# HV_Side.net
KiCad netlist of a schematic drawn in Altium Designer
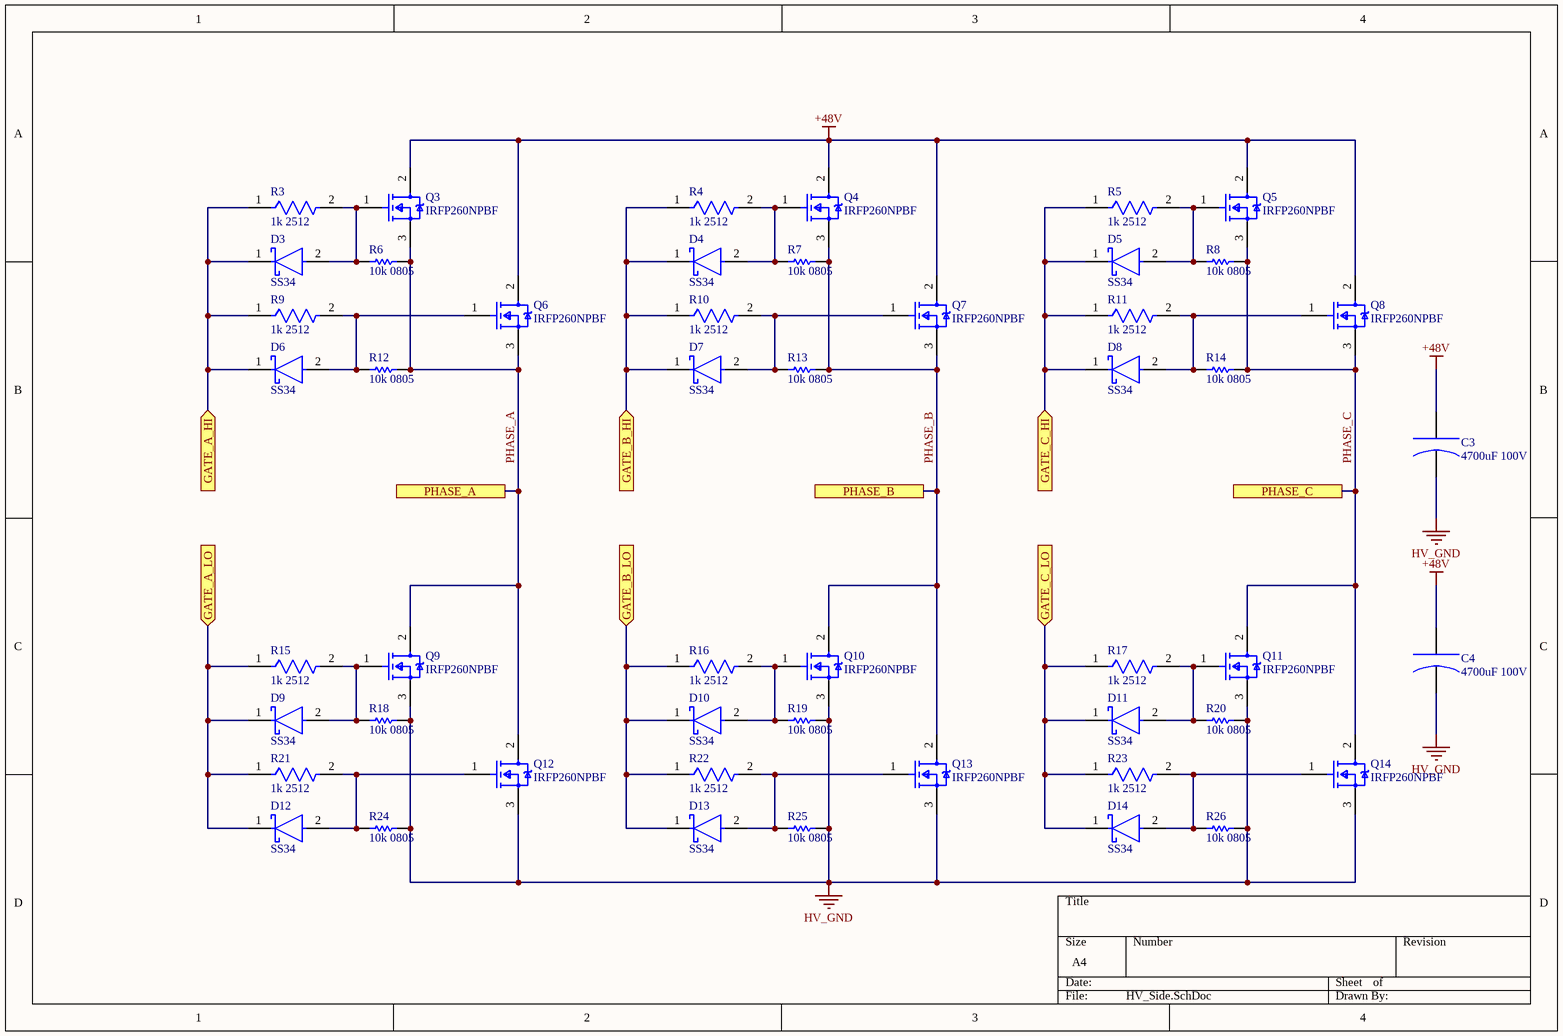
[diagram p0: HV_Side.SchDoc]

(export (version "E")
  (design (tool "Eeschema 10.0.6"))
  (components
    (comp (ref "C3")
      (value "4700uF 100V")
      (footprint "4700uF 100V")
      (description "4700uF 100V Electrolytic Capacitor")
      (libsource (lib "1kW_BLDC_Controller") (part "4700uF 100V"))
    )
    (comp (ref "C4")
      (value "4700uF 100V")
      (footprint "4700uF 100V")
      (description "4700uF 100V Electrolytic Capacitor")
      (libsource (lib "1kW_BLDC_Controller") (part "4700uF 100V"))
    )
    (comp (ref "D3")
      (value "SS34")
      (footprint "DO-214AC")
      (description "SS34 SMA 40V/3A Schottky Diode SMD Package-DO-214AC")
      (fields
        (field (name "MANUFACTURER") "Vishay Semiconductors")
        (field (name "MANUFACTURER PART NUMBER") "SS34-E3/57T")
      )
      (libsource (lib "1kW_BLDC_Controller") (part "SS34"))
    )
    (comp (ref "D4")
      (value "SS34")
      (footprint "DO-214AC")
      (description "SS34 SMA 40V/3A Schottky Diode SMD Package-DO-214AC")
      (fields
        (field (name "MANUFACTURER") "Vishay Semiconductors")
        (field (name "MANUFACTURER PART NUMBER") "SS34-E3/57T")
      )
      (libsource (lib "1kW_BLDC_Controller") (part "SS34"))
    )
    (comp (ref "D5")
      (value "SS34")
      (footprint "DO-214AC")
      (description "SS34 SMA 40V/3A Schottky Diode SMD Package-DO-214AC")
      (fields
        (field (name "MANUFACTURER") "Vishay Semiconductors")
        (field (name "MANUFACTURER PART NUMBER") "SS34-E3/57T")
      )
      (libsource (lib "1kW_BLDC_Controller") (part "SS34"))
    )
    (comp (ref "D6")
      (value "SS34")
      (footprint "DO-214AC")
      (description "SS34 SMA 40V/3A Schottky Diode SMD Package-DO-214AC")
      (fields
        (field (name "MANUFACTURER") "Vishay Semiconductors")
        (field (name "MANUFACTURER PART NUMBER") "SS34-E3/57T")
      )
      (libsource (lib "1kW_BLDC_Controller") (part "SS34"))
    )
    (comp (ref "D7")
      (value "SS34")
      (footprint "DO-214AC")
      (description "SS34 SMA 40V/3A Schottky Diode SMD Package-DO-214AC")
      (fields
        (field (name "MANUFACTURER") "Vishay Semiconductors")
        (field (name "MANUFACTURER PART NUMBER") "SS34-E3/57T")
      )
      (libsource (lib "1kW_BLDC_Controller") (part "SS34"))
    )
    (comp (ref "D8")
      (value "SS34")
      (footprint "DO-214AC")
      (description "SS34 SMA 40V/3A Schottky Diode SMD Package-DO-214AC")
      (fields
        (field (name "MANUFACTURER") "Vishay Semiconductors")
        (field (name "MANUFACTURER PART NUMBER") "SS34-E3/57T")
      )
      (libsource (lib "1kW_BLDC_Controller") (part "SS34"))
    )
    (comp (ref "D9")
      (value "SS34")
      (footprint "DO-214AC")
      (description "SS34 SMA 40V/3A Schottky Diode SMD Package-DO-214AC")
      (fields
        (field (name "MANUFACTURER") "Vishay Semiconductors")
        (field (name "MANUFACTURER PART NUMBER") "SS34-E3/57T")
      )
      (libsource (lib "1kW_BLDC_Controller") (part "SS34"))
    )
    (comp (ref "D10")
      (value "SS34")
      (footprint "DO-214AC")
      (description "SS34 SMA 40V/3A Schottky Diode SMD Package-DO-214AC")
      (fields
        (field (name "MANUFACTURER") "Vishay Semiconductors")
        (field (name "MANUFACTURER PART NUMBER") "SS34-E3/57T")
      )
      (libsource (lib "1kW_BLDC_Controller") (part "SS34"))
    )
    (comp (ref "D11")
      (value "SS34")
      (footprint "DO-214AC")
      (description "SS34 SMA 40V/3A Schottky Diode SMD Package-DO-214AC")
      (fields
        (field (name "MANUFACTURER") "Vishay Semiconductors")
        (field (name "MANUFACTURER PART NUMBER") "SS34-E3/57T")
      )
      (libsource (lib "1kW_BLDC_Controller") (part "SS34"))
    )
    (comp (ref "D12")
      (value "SS34")
      (footprint "DO-214AC")
      (description "SS34 SMA 40V/3A Schottky Diode SMD Package-DO-214AC")
      (fields
        (field (name "MANUFACTURER") "Vishay Semiconductors")
        (field (name "MANUFACTURER PART NUMBER") "SS34-E3/57T")
      )
      (libsource (lib "1kW_BLDC_Controller") (part "SS34"))
    )
    (comp (ref "D13")
      (value "SS34")
      (footprint "DO-214AC")
      (description "SS34 SMA 40V/3A Schottky Diode SMD Package-DO-214AC")
      (fields
        (field (name "MANUFACTURER") "Vishay Semiconductors")
        (field (name "MANUFACTURER PART NUMBER") "SS34-E3/57T")
      )
      (libsource (lib "1kW_BLDC_Controller") (part "SS34"))
    )
    (comp (ref "D14")
      (value "SS34")
      (footprint "DO-214AC")
      (description "SS34 SMA 40V/3A Schottky Diode SMD Package-DO-214AC")
      (fields
        (field (name "MANUFACTURER") "Vishay Semiconductors")
        (field (name "MANUFACTURER PART NUMBER") "SS34-E3/57T")
      )
      (libsource (lib "1kW_BLDC_Controller") (part "SS34"))
    )
    (comp (ref "Q3")
      (value "IRFP260NPBF")
      (footprint "FP-PG-TO247-3-MFG")
      (description "MOSFET N-CH 200V 50A TO247AC")
      (libsource (lib "Altium Content Vault") (part "b09f7f152735e370c1ea22a33fa83d6"))
    )
    (comp (ref "Q4")
      (value "IRFP260NPBF")
      (footprint "FP-PG-TO247-3-MFG")
      (description "MOSFET N-CH 200V 50A TO247AC")
      (libsource (lib "Altium Content Vault") (part "b09f7f152735e370c1ea22a33fa83d6"))
    )
    (comp (ref "Q5")
      (value "IRFP260NPBF")
      (footprint "FP-PG-TO247-3-MFG")
      (description "MOSFET N-CH 200V 50A TO247AC")
      (libsource (lib "Altium Content Vault") (part "b09f7f152735e370c1ea22a33fa83d6"))
    )
    (comp (ref "Q6")
      (value "IRFP260NPBF")
      (footprint "FP-PG-TO247-3-MFG")
      (description "MOSFET N-CH 200V 50A TO247AC")
      (libsource (lib "Altium Content Vault") (part "b09f7f152735e370c1ea22a33fa83d6"))
    )
    (comp (ref "Q7")
      (value "IRFP260NPBF")
      (footprint "FP-PG-TO247-3-MFG")
      (description "MOSFET N-CH 200V 50A TO247AC")
      (libsource (lib "Altium Content Vault") (part "b09f7f152735e370c1ea22a33fa83d6"))
    )
    (comp (ref "Q8")
      (value "IRFP260NPBF")
      (footprint "FP-PG-TO247-3-MFG")
      (description "MOSFET N-CH 200V 50A TO247AC")
      (libsource (lib "Altium Content Vault") (part "b09f7f152735e370c1ea22a33fa83d6"))
    )
    (comp (ref "Q9")
      (value "IRFP260NPBF")
      (footprint "FP-PG-TO247-3-MFG")
      (description "MOSFET N-CH 200V 50A TO247AC")
      (libsource (lib "Altium Content Vault") (part "b09f7f152735e370c1ea22a33fa83d6"))
    )
    (comp (ref "Q10")
      (value "IRFP260NPBF")
      (footprint "FP-PG-TO247-3-MFG")
      (description "MOSFET N-CH 200V 50A TO247AC")
      (libsource (lib "Altium Content Vault") (part "b09f7f152735e370c1ea22a33fa83d6"))
    )
    (comp (ref "Q11")
      (value "IRFP260NPBF")
      (footprint "FP-PG-TO247-3-MFG")
      (description "MOSFET N-CH 200V 50A TO247AC")
      (libsource (lib "Altium Content Vault") (part "b09f7f152735e370c1ea22a33fa83d6"))
    )
    (comp (ref "Q12")
      (value "IRFP260NPBF")
      (footprint "FP-PG-TO247-3-MFG")
      (description "MOSFET N-CH 200V 50A TO247AC")
      (libsource (lib "Altium Content Vault") (part "b09f7f152735e370c1ea22a33fa83d6"))
    )
    (comp (ref "Q13")
      (value "IRFP260NPBF")
      (footprint "FP-PG-TO247-3-MFG")
      (description "MOSFET N-CH 200V 50A TO247AC")
      (libsource (lib "Altium Content Vault") (part "b09f7f152735e370c1ea22a33fa83d6"))
    )
    (comp (ref "Q14")
      (value "IRFP260NPBF")
      (footprint "FP-PG-TO247-3-MFG")
      (description "MOSFET N-CH 200V 50A TO247AC")
      (libsource (lib "Altium Content Vault") (part "b09f7f152735e370c1ea22a33fa83d6"))
    )
    (comp (ref "R3")
      (value "1k 2512")
      (footprint "R2512")
      (description "1K Ohm 1W Resistor 2512 Package")
      (fields (field (name "TOLERANCE") "1%") (field (name "MANUFACTURER") "Vishay Dale"))
      (libsource (lib "1kW_BLDC_Controller") (part "1K_2512"))
    )
    (comp (ref "R4")
      (value "1k 2512")
      (footprint "R2512")
      (description "1K Ohm 1W Resistor 2512 Package")
      (fields (field (name "TOLERANCE") "1%") (field (name "MANUFACTURER") "Vishay Dale"))
      (libsource (lib "1kW_BLDC_Controller") (part "1K_2512"))
    )
    (comp (ref "R5")
      (value "1k 2512")
      (footprint "R2512")
      (description "1K Ohm 1W Resistor 2512 Package")
      (fields (field (name "TOLERANCE") "1%") (field (name "MANUFACTURER") "Vishay Dale"))
      (libsource (lib "1kW_BLDC_Controller") (part "1K_2512"))
    )
    (comp (ref "R6")
      (value "10k 0805")
      (footprint "R0805")
      (description "10K Ohm 1/8 Watt Resistor 1% Tolerance RC0805FR-0710KL – 0805 Package")
      (libsource (lib "1kW_BLDC_Controller") (part "10k 0805"))
    )
    (comp (ref "R7")
      (value "10k 0805")
      (footprint "R0805")
      (description "10K Ohm 1/8 Watt Resistor 1% Tolerance RC0805FR-0710KL – 0805 Package")
      (libsource (lib "1kW_BLDC_Controller") (part "10k 0805"))
    )
    (comp (ref "R8")
      (value "10k 0805")
      (footprint "R0805")
      (description "10K Ohm 1/8 Watt Resistor 1% Tolerance RC0805FR-0710KL – 0805 Package")
      (libsource (lib "1kW_BLDC_Controller") (part "10k 0805"))
    )
    (comp (ref "R9")
      (value "1k 2512")
      (footprint "R2512")
      (description "1K Ohm 1W Resistor 2512 Package")
      (fields (field (name "TOLERANCE") "1%") (field (name "MANUFACTURER") "Vishay Dale"))
      (libsource (lib "1kW_BLDC_Controller") (part "1K_2512"))
    )
    (comp (ref "R10")
      (value "1k 2512")
      (footprint "R2512")
      (description "1K Ohm 1W Resistor 2512 Package")
      (fields (field (name "TOLERANCE") "1%") (field (name "MANUFACTURER") "Vishay Dale"))
      (libsource (lib "1kW_BLDC_Controller") (part "1K_2512"))
    )
    (comp (ref "R11")
      (value "1k 2512")
      (footprint "R2512")
      (description "1K Ohm 1W Resistor 2512 Package")
      (fields (field (name "TOLERANCE") "1%") (field (name "MANUFACTURER") "Vishay Dale"))
      (libsource (lib "1kW_BLDC_Controller") (part "1K_2512"))
    )
    (comp (ref "R12")
      (value "10k 0805")
      (footprint "R0805")
      (description "10K Ohm 1/8 Watt Resistor 1% Tolerance RC0805FR-0710KL – 0805 Package")
      (libsource (lib "1kW_BLDC_Controller") (part "10k 0805"))
    )
    (comp (ref "R13")
      (value "10k 0805")
      (footprint "R0805")
      (description "10K Ohm 1/8 Watt Resistor 1% Tolerance RC0805FR-0710KL – 0805 Package")
      (libsource (lib "1kW_BLDC_Controller") (part "10k 0805"))
    )
    (comp (ref "R14")
      (value "10k 0805")
      (footprint "R0805")
      (description "10K Ohm 1/8 Watt Resistor 1% Tolerance RC0805FR-0710KL – 0805 Package")
      (libsource (lib "1kW_BLDC_Controller") (part "10k 0805"))
    )
    (comp (ref "R15")
      (value "1k 2512")
      (footprint "R2512")
      (description "1K Ohm 1W Resistor 2512 Package")
      (fields (field (name "TOLERANCE") "1%") (field (name "MANUFACTURER") "Vishay Dale"))
      (libsource (lib "1kW_BLDC_Controller") (part "1K_2512"))
    )
    (comp (ref "R16")
      (value "1k 2512")
      (footprint "R2512")
      (description "1K Ohm 1W Resistor 2512 Package")
      (fields (field (name "TOLERANCE") "1%") (field (name "MANUFACTURER") "Vishay Dale"))
      (libsource (lib "1kW_BLDC_Controller") (part "1K_2512"))
    )
    (comp (ref "R17")
      (value "1k 2512")
      (footprint "R2512")
      (description "1K Ohm 1W Resistor 2512 Package")
      (fields (field (name "TOLERANCE") "1%") (field (name "MANUFACTURER") "Vishay Dale"))
      (libsource (lib "1kW_BLDC_Controller") (part "1K_2512"))
    )
    (comp (ref "R18")
      (value "10k 0805")
      (footprint "R0805")
      (description "10K Ohm 1/8 Watt Resistor 1% Tolerance RC0805FR-0710KL – 0805 Package")
      (libsource (lib "1kW_BLDC_Controller") (part "10k 0805"))
    )
    (comp (ref "R19")
      (value "10k 0805")
      (footprint "R0805")
      (description "10K Ohm 1/8 Watt Resistor 1% Tolerance RC0805FR-0710KL – 0805 Package")
      (libsource (lib "1kW_BLDC_Controller") (part "10k 0805"))
    )
    (comp (ref "R20")
      (value "10k 0805")
      (footprint "R0805")
      (description "10K Ohm 1/8 Watt Resistor 1% Tolerance RC0805FR-0710KL – 0805 Package")
      (libsource (lib "1kW_BLDC_Controller") (part "10k 0805"))
    )
    (comp (ref "R21")
      (value "1k 2512")
      (footprint "R2512")
      (description "1K Ohm 1W Resistor 2512 Package")
      (fields (field (name "TOLERANCE") "1%") (field (name "MANUFACTURER") "Vishay Dale"))
      (libsource (lib "1kW_BLDC_Controller") (part "1K_2512"))
    )
    (comp (ref "R22")
      (value "1k 2512")
      (footprint "R2512")
      (description "1K Ohm 1W Resistor 2512 Package")
      (fields (field (name "TOLERANCE") "1%") (field (name "MANUFACTURER") "Vishay Dale"))
      (libsource (lib "1kW_BLDC_Controller") (part "1K_2512"))
    )
    (comp (ref "R23")
      (value "1k 2512")
      (footprint "R2512")
      (description "1K Ohm 1W Resistor 2512 Package")
      (fields (field (name "TOLERANCE") "1%") (field (name "MANUFACTURER") "Vishay Dale"))
      (libsource (lib "1kW_BLDC_Controller") (part "1K_2512"))
    )
    (comp (ref "R24")
      (value "10k 0805")
      (footprint "R0805")
      (description "10K Ohm 1/8 Watt Resistor 1% Tolerance RC0805FR-0710KL – 0805 Package")
      (libsource (lib "1kW_BLDC_Controller") (part "10k 0805"))
    )
    (comp (ref "R25")
      (value "10k 0805")
      (footprint "R0805")
      (description "10K Ohm 1/8 Watt Resistor 1% Tolerance RC0805FR-0710KL – 0805 Package")
      (libsource (lib "1kW_BLDC_Controller") (part "10k 0805"))
    )
    (comp (ref "R26")
      (value "10k 0805")
      (footprint "R0805")
      (description "10K Ohm 1/8 Watt Resistor 1% Tolerance RC0805FR-0710KL – 0805 Package")
      (libsource (lib "1kW_BLDC_Controller") (part "10k 0805"))
    )
  )
  (nets
    (net (code "1") (name "+48V") (class "Default")
      (node (ref "C3") (pin "1") (pinfunction "+_1") (pintype "power_in"))
      (node (ref "C4") (pin "1") (pinfunction "+_1") (pintype "power_in"))
      (node (ref "Q3") (pin "2") (pinfunction "D_2") (pintype "passive"))
      (node (ref "Q4") (pin "2") (pinfunction "D_2") (pintype "passive"))
      (node (ref "Q5") (pin "2") (pinfunction "D_2") (pintype "passive"))
      (node (ref "Q6") (pin "2") (pinfunction "D_2") (pintype "passive"))
      (node (ref "Q7") (pin "2") (pinfunction "D_2") (pintype "passive"))
      (node (ref "Q8") (pin "2") (pinfunction "D_2") (pintype "passive"))
    )
    (net (code "2") (name "/GATE_A_HI") (class "Default")
      (node (ref "D3") (pin "1") (pinfunction "C_1") (pintype "passive"))
      (node (ref "D6") (pin "1") (pinfunction "C_1") (pintype "passive"))
      (node (ref "R3") (pin "1") (pinfunction "1_1") (pintype "passive"))
      (node (ref "R9") (pin "1") (pinfunction "1_1") (pintype "passive"))
    )
    (net (code "3") (name "/GATE_A_LO") (class "Default")
      (node (ref "D12") (pin "1") (pinfunction "C_1") (pintype "passive"))
      (node (ref "D9") (pin "1") (pinfunction "C_1") (pintype "passive"))
      (node (ref "R15") (pin "1") (pinfunction "1_1") (pintype "passive"))
      (node (ref "R21") (pin "1") (pinfunction "1_1") (pintype "passive"))
    )
    (net (code "4") (name "/GATE_B_HI") (class "Default")
      (node (ref "D4") (pin "1") (pinfunction "C_1") (pintype "passive"))
      (node (ref "D7") (pin "1") (pinfunction "C_1") (pintype "passive"))
      (node (ref "R10") (pin "1") (pinfunction "1_1") (pintype "passive"))
      (node (ref "R4") (pin "1") (pinfunction "1_1") (pintype "passive"))
    )
    (net (code "5") (name "/GATE_B_LO") (class "Default")
      (node (ref "D10") (pin "1") (pinfunction "C_1") (pintype "passive"))
      (node (ref "D13") (pin "1") (pinfunction "C_1") (pintype "passive"))
      (node (ref "R16") (pin "1") (pinfunction "1_1") (pintype "passive"))
      (node (ref "R22") (pin "1") (pinfunction "1_1") (pintype "passive"))
    )
    (net (code "6") (name "/GATE_C_HI") (class "Default")
      (node (ref "D5") (pin "1") (pinfunction "C_1") (pintype "passive"))
      (node (ref "D8") (pin "1") (pinfunction "C_1") (pintype "passive"))
      (node (ref "R11") (pin "1") (pinfunction "1_1") (pintype "passive"))
      (node (ref "R5") (pin "1") (pinfunction "1_1") (pintype "passive"))
    )
    (net (code "7") (name "/GATE_C_LO") (class "Default")
      (node (ref "D11") (pin "1") (pinfunction "C_1") (pintype "passive"))
      (node (ref "D14") (pin "1") (pinfunction "C_1") (pintype "passive"))
      (node (ref "R17") (pin "1") (pinfunction "1_1") (pintype "passive"))
      (node (ref "R23") (pin "1") (pinfunction "1_1") (pintype "passive"))
    )
    (net (code "8") (name "/PHASE_A") (class "Default")
      (node (ref "Q12") (pin "2") (pinfunction "D_2") (pintype "passive"))
      (node (ref "Q3") (pin "3") (pinfunction "S_3") (pintype "passive"))
      (node (ref "Q6") (pin "3") (pinfunction "S_3") (pintype "passive"))
      (node (ref "Q9") (pin "2") (pinfunction "D_2") (pintype "passive"))
      (node (ref "R12") (pin "2") (pinfunction "2_2") (pintype "passive"))
      (node (ref "R6") (pin "2") (pinfunction "2_2") (pintype "passive"))
    )
    (net (code "9") (name "/PHASE_B") (class "Default")
      (node (ref "Q10") (pin "2") (pinfunction "D_2") (pintype "passive"))
      (node (ref "Q13") (pin "2") (pinfunction "D_2") (pintype "passive"))
      (node (ref "Q4") (pin "3") (pinfunction "S_3") (pintype "passive"))
      (node (ref "Q7") (pin "3") (pinfunction "S_3") (pintype "passive"))
      (node (ref "R13") (pin "2") (pinfunction "2_2") (pintype "passive"))
      (node (ref "R7") (pin "2") (pinfunction "2_2") (pintype "passive"))
    )
    (net (code "10") (name "/PHASE_C") (class "Default")
      (node (ref "Q11") (pin "2") (pinfunction "D_2") (pintype "passive"))
      (node (ref "Q14") (pin "2") (pinfunction "D_2") (pintype "passive"))
      (node (ref "Q5") (pin "3") (pinfunction "S_3") (pintype "passive"))
      (node (ref "Q8") (pin "3") (pinfunction "S_3") (pintype "passive"))
      (node (ref "R14") (pin "2") (pinfunction "2_2") (pintype "passive"))
      (node (ref "R8") (pin "2") (pinfunction "2_2") (pintype "passive"))
    )
    (net (code "11") (name "HV_GND") (class "Default")
      (node (ref "C3") (pin "2") (pinfunction "GND_2") (pintype "power_in"))
      (node (ref "C4") (pin "2") (pinfunction "GND_2") (pintype "power_in"))
      (node (ref "Q10") (pin "3") (pinfunction "S_3") (pintype "passive"))
      (node (ref "Q11") (pin "3") (pinfunction "S_3") (pintype "passive"))
      (node (ref "Q12") (pin "3") (pinfunction "S_3") (pintype "passive"))
      (node (ref "Q13") (pin "3") (pinfunction "S_3") (pintype "passive"))
      (node (ref "Q14") (pin "3") (pinfunction "S_3") (pintype "passive"))
      (node (ref "Q9") (pin "3") (pinfunction "S_3") (pintype "passive"))
      (node (ref "R18") (pin "2") (pinfunction "2_2") (pintype "passive"))
      (node (ref "R19") (pin "2") (pinfunction "2_2") (pintype "passive"))
      (node (ref "R20") (pin "2") (pinfunction "2_2") (pintype "passive"))
      (node (ref "R24") (pin "2") (pinfunction "2_2") (pintype "passive"))
      (node (ref "R25") (pin "2") (pinfunction "2_2") (pintype "passive"))
      (node (ref "R26") (pin "2") (pinfunction "2_2") (pintype "passive"))
    )
    (net (code "12") (name "Net-(D3-A)") (class "Default")
      (node (ref "D3") (pin "2") (pinfunction "A_2") (pintype "passive"))
      (node (ref "Q3") (pin "1") (pinfunction "G_1") (pintype "passive"))
      (node (ref "R3") (pin "2") (pinfunction "2_2") (pintype "passive"))
      (node (ref "R6") (pin "1") (pinfunction "1_1") (pintype "passive"))
    )
    (net (code "13") (name "Net-(D4-A)") (class "Default")
      (node (ref "D4") (pin "2") (pinfunction "A_2") (pintype "passive"))
      (node (ref "Q4") (pin "1") (pinfunction "G_1") (pintype "passive"))
      (node (ref "R4") (pin "2") (pinfunction "2_2") (pintype "passive"))
      (node (ref "R7") (pin "1") (pinfunction "1_1") (pintype "passive"))
    )
    (net (code "14") (name "Net-(D5-A)") (class "Default")
      (node (ref "D5") (pin "2") (pinfunction "A_2") (pintype "passive"))
      (node (ref "Q5") (pin "1") (pinfunction "G_1") (pintype "passive"))
      (node (ref "R5") (pin "2") (pinfunction "2_2") (pintype "passive"))
      (node (ref "R8") (pin "1") (pinfunction "1_1") (pintype "passive"))
    )
    (net (code "15") (name "Net-(D6-A)") (class "Default")
      (node (ref "D6") (pin "2") (pinfunction "A_2") (pintype "passive"))
      (node (ref "Q6") (pin "1") (pinfunction "G_1") (pintype "passive"))
      (node (ref "R12") (pin "1") (pinfunction "1_1") (pintype "passive"))
      (node (ref "R9") (pin "2") (pinfunction "2_2") (pintype "passive"))
    )
    (net (code "16") (name "Net-(D7-A)") (class "Default")
      (node (ref "D7") (pin "2") (pinfunction "A_2") (pintype "passive"))
      (node (ref "Q7") (pin "1") (pinfunction "G_1") (pintype "passive"))
      (node (ref "R10") (pin "2") (pinfunction "2_2") (pintype "passive"))
      (node (ref "R13") (pin "1") (pinfunction "1_1") (pintype "passive"))
    )
    (net (code "17") (name "Net-(D8-A)") (class "Default")
      (node (ref "D8") (pin "2") (pinfunction "A_2") (pintype "passive"))
      (node (ref "Q8") (pin "1") (pinfunction "G_1") (pintype "passive"))
      (node (ref "R11") (pin "2") (pinfunction "2_2") (pintype "passive"))
      (node (ref "R14") (pin "1") (pinfunction "1_1") (pintype "passive"))
    )
    (net (code "18") (name "Net-(D9-A)") (class "Default")
      (node (ref "D9") (pin "2") (pinfunction "A_2") (pintype "passive"))
      (node (ref "Q9") (pin "1") (pinfunction "G_1") (pintype "passive"))
      (node (ref "R15") (pin "2") (pinfunction "2_2") (pintype "passive"))
      (node (ref "R18") (pin "1") (pinfunction "1_1") (pintype "passive"))
    )
    (net (code "19") (name "Net-(D10-A)") (class "Default")
      (node (ref "D10") (pin "2") (pinfunction "A_2") (pintype "passive"))
      (node (ref "Q10") (pin "1") (pinfunction "G_1") (pintype "passive"))
      (node (ref "R16") (pin "2") (pinfunction "2_2") (pintype "passive"))
      (node (ref "R19") (pin "1") (pinfunction "1_1") (pintype "passive"))
    )
    (net (code "20") (name "Net-(D11-A)") (class "Default")
      (node (ref "D11") (pin "2") (pinfunction "A_2") (pintype "passive"))
      (node (ref "Q11") (pin "1") (pinfunction "G_1") (pintype "passive"))
      (node (ref "R17") (pin "2") (pinfunction "2_2") (pintype "passive"))
      (node (ref "R20") (pin "1") (pinfunction "1_1") (pintype "passive"))
    )
    (net (code "21") (name "Net-(D12-A)") (class "Default")
      (node (ref "D12") (pin "2") (pinfunction "A_2") (pintype "passive"))
      (node (ref "Q12") (pin "1") (pinfunction "G_1") (pintype "passive"))
      (node (ref "R21") (pin "2") (pinfunction "2_2") (pintype "passive"))
      (node (ref "R24") (pin "1") (pinfunction "1_1") (pintype "passive"))
    )
    (net (code "22") (name "Net-(D13-A)") (class "Default")
      (node (ref "D13") (pin "2") (pinfunction "A_2") (pintype "passive"))
      (node (ref "Q13") (pin "1") (pinfunction "G_1") (pintype "passive"))
      (node (ref "R22") (pin "2") (pinfunction "2_2") (pintype "passive"))
      (node (ref "R25") (pin "1") (pinfunction "1_1") (pintype "passive"))
    )
    (net (code "23") (name "Net-(D14-A)") (class "Default")
      (node (ref "D14") (pin "2") (pinfunction "A_2") (pintype "passive"))
      (node (ref "Q14") (pin "1") (pinfunction "G_1") (pintype "passive"))
      (node (ref "R23") (pin "2") (pinfunction "2_2") (pintype "passive"))
      (node (ref "R26") (pin "1") (pinfunction "1_1") (pintype "passive"))
    )
  )
)
